# Power.net
KiCad netlist of a schematic drawn in Altium Designer
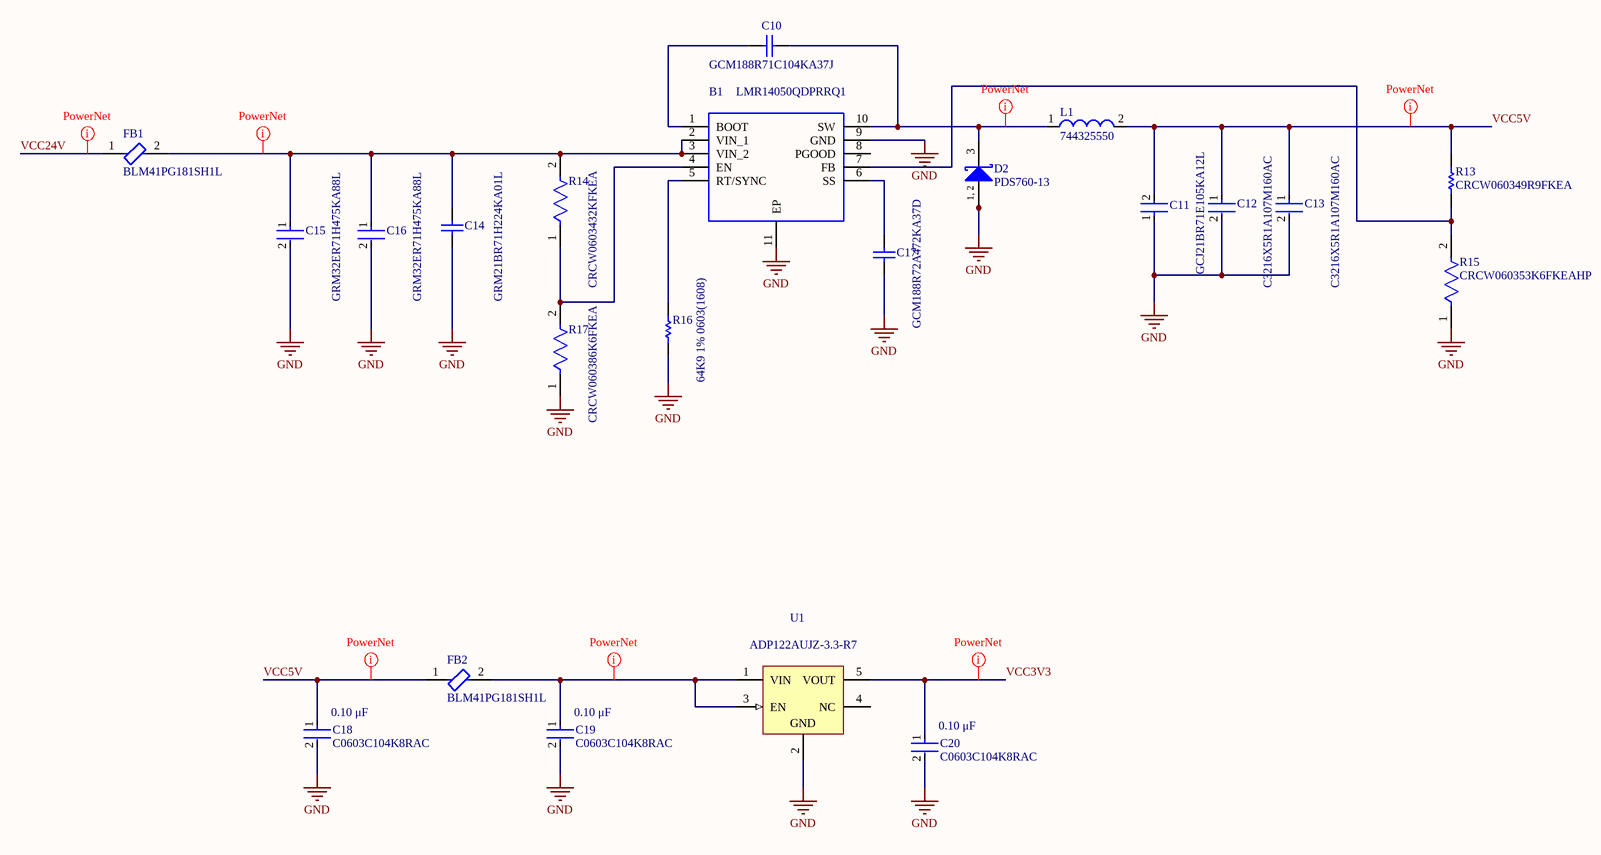
[diagram p0: Power.SchDoc]

(export (version "E")
  (design (tool "Eeschema 10.0.6"))
  (components
    (comp (ref "B1")
      (value "LMR14050QDPRRQ1")
      (footprint "SON80P400X400X80-11N")
      (description "Automotive 40V, 5A SIMPLE SWITCHER&#174;, 2.2MHz Step-Down Regulator with 40uA IQ")
      (fields (field (name "MOUSER PART NUMBER") "595-LMR14050QDPRRQ1"))
      (libsource (lib "Schlib2") (part "LMR14050QDPRRQ1"))
    )
    (comp (ref "C10")
      (value "GCM188R71C104KA37J")
      (footprint "CAPC1608X90X35LL10T15")
      (fields (field (name "MANUFACTURER") "Murata"))
      (libsource (lib "Altium Content Vault") (part "CAP"))
    )
    (comp (ref "C11")
      (value "GCJ21BR71E105KA12L")
      (footprint "FP-GCJ21B-0_3-MFG")
      (description "Multilayer Ceramic Capacitors MLCC - SMD/SMT 0805 1uF 10%, 25VDC,  X7R 15%")
      (fields (field (name "TOLERANCE") "10%"))
      (libsource (lib "Altium Content Vault") (part "02cd4be3c70576c341d710602a673aa"))
    )
    (comp (ref "C12")
      (value "C3216X5R1A107M160AC")
      (footprint "FP-C3216-160-0_3-IPC_C")
      (description "Multilayer Ceramic Capacitors 100uF ±20% 10V X5R SMD 1206")
      (fields (field (name "VOLTAGE") "10V") (field (name "TOLERANCE") "20%"))
      (libsource (lib "Altium Content Vault") (part "02cd4be3c70576c341d710602a673aa"))
    )
    (comp (ref "C13")
      (value "C3216X5R1A107M160AC")
      (footprint "FP-C3216-160-0_3-IPC_C")
      (description "Multilayer Ceramic Capacitors 100uF ±20% 10V X5R SMD 1206")
      (fields (field (name "VOLTAGE") "10V") (field (name "TOLERANCE") "20%"))
      (libsource (lib "Altium Content Vault") (part "02cd4be3c70576c341d710602a673aa"))
    )
    (comp (ref "C14")
      (value "GRM21BR71H224KA01L")
      (footprint "CAPC2013X135X45NL10T25")
      (fields (field (name "MANUFACTURER") "Murata"))
      (libsource (lib "Altium Content Vault") (part "CAP"))
    )
    (comp (ref "C15")
      (value "GRM32ER71H475KA88L")
      (footprint "FP-GRM32-MFG")
      (description "CAP CER 4.7UF 50V X7R 1210")
      (fields (field (name "MANUFACTURER") "Murata") (field (name "TOLERANCE") "10%"))
      (libsource (lib "Altium Content Vault") (part "b4654b650e69147ec39a6b967a45e02"))
    )
    (comp (ref "C16")
      (value "GRM32ER71H475KA88L")
      (footprint "FP-GRM32-MFG")
      (description "CAP CER 4.7UF 50V X7R 1210")
      (fields (field (name "MANUFACTURER") "Murata") (field (name "TOLERANCE") "10%"))
      (libsource (lib "Altium Content Vault") (part "b4654b650e69147ec39a6b967a45e02"))
    )
    (comp (ref "C17")
      (value "GCM188R72A472KA37D")
      (footprint "CAPC1608X90X35ML10T15")
      (fields (field (name "MANUFACTURER") "Murata"))
      (libsource (lib "Altium Content Vault") (part "CAP"))
    )
    (comp (ref "C18")
      (value "C0603C104K8RAC")
      (footprint "FP-C0603C-CF-MFG")
      (description "C0603 0.10 μF X7R 30ppm/°C 10.00% 10 V")
      (fields
        (field (name "MANUFACTURER") "KEMET")
        (field (name "CAPACITANCE") "0.10 μF")
        (field (name "OCTOPART") "https://octopart.com/c0603c104k8rac-kemet-1325403")
      )
      (libsource (lib "Altium Content Vault") (part "b4654b650e69147ec39a6b967a45e02"))
    )
    (comp (ref "C19")
      (value "C0603C104K8RAC")
      (footprint "FP-C0603C-CF-MFG")
      (description "C0603 0.10 μF X7R 30ppm/°C 10.00% 10 V")
      (fields
        (field (name "MANUFACTURER") "KEMET")
        (field (name "CAPACITANCE") "0.10 μF")
        (field (name "OCTOPART") "https://octopart.com/c0603c104k8rac-kemet-1325403")
      )
      (libsource (lib "Altium Content Vault") (part "b4654b650e69147ec39a6b967a45e02"))
    )
    (comp (ref "C20")
      (value "C0603C104K8RAC")
      (footprint "FP-C0603C-CF-MFG")
      (description "C0603 0.10 μF X7R 30ppm/°C 10.00% 10 V")
      (fields
        (field (name "MANUFACTURER") "KEMET")
        (field (name "CAPACITANCE") "0.10 μF")
        (field (name "OCTOPART") "https://octopart.com/c0603c104k8rac-kemet-1325403")
      )
      (libsource (lib "Altium Content Vault") (part "b4654b650e69147ec39a6b967a45e02"))
    )
    (comp (ref "D2")
      (value "PDS760-13")
      (footprint "DIOD-POWERDI5-3_V")
      (description "Schottky Barrier Rectifier, 60 V, 7 A, -65 to 150 degC, 3-Pin SMD, RoHS, Tape and Reel")
      (fields (field (name "MANUFACTURER") "Diodes Inc"))
      (libsource (lib "Altium Content Vault") (part "DSKY-AAK-3_A"))
    )
    (comp (ref "FB1")
      (value "BLM41PG181SH1L")
      (footprint "FP-BLM41-0_2-a1_2-MFG")
      (description "Ferrite Bead, 1806, 180Ω @ 100MHz, 25%, 0.02Ω, 3.5A")
      (fields (field (name "TOLERANCE") "25%"))
      (libsource (lib "Altium Content Vault") (part "5f30dd21d616792df468990f7003faa"))
    )
    (comp (ref "FB2")
      (value "BLM41PG181SH1L")
      (footprint "FP-BLM41-0_2-a1_2-MFG")
      (description "Ferrite Bead, 1806, 180Ω @ 100MHz, 25%, 0.02Ω, 3.5A")
      (fields (field (name "TOLERANCE") "25%"))
      (libsource (lib "Altium Content Vault") (part "5f30dd21d616792df468990f7003faa"))
    )
    (comp (ref "L1")
      (value "744325550")
      (footprint "WE-HCI-1050")
      (description "SMD Flat Wire High Current Inductor WE-HCI, L=5.50 µH")
      (libsource (lib "Altium Content Vault") (part "PAS-IND-INDUCTOR-2"))
    )
    (comp (ref "R13")
      (value "CRCW060349R9FKEA")
      (footprint "RESC1609X50X30ML10T20")
      (fields (field (name "MANUFACTURER") "Vishay Dale"))
      (libsource (lib "Altium Content Vault") (part "RES"))
    )
    (comp (ref "R14")
      (value "CRCW0603432KFKEA")
      (footprint "FP-CRCW0603-e3-MFG")
      (description "RES Thick Film, 432kΩ, 1%, 0.1W, 100ppm/°C, 0603")
      (fields (field (name "TOLERANCE") "1%"))
      (libsource (lib "Altium Content Vault") (part "1029c3af85768c4190bb7ad29bc67b5"))
    )
    (comp (ref "R15")
      (value "CRCW060353K6FKEAHP")
      (footprint "FP-CRCW0603-HPe3-MFG")
      (description "RES Thick Film, 53.6kΩ, 1%, 0.33W, 100ppm/°C, 0603")
      (fields (field (name "TOLERANCE") "1%"))
      (libsource (lib "Altium Content Vault") (part "1029c3af85768c4190bb7ad29bc67b5"))
    )
    (comp (ref "R16")
      (value "64K9 1% 0603(1608)")
      (footprint "RESC0603(1608)_N")
      (description "64K9 0.1W 1% 0603 (1608 Metric)  SMD")
      (fields (field (name "TOLERANCE") "1 %") (field (name "POWER") "0.1 W"))
      (libsource (lib "Altium Content Vault") (part "RES"))
    )
    (comp (ref "R17")
      (value "CRCW060386K6FKEA")
      (footprint "FP-CRCW0603-e3-IPC_B")
      (description "RES Thick Film, 86.6kΩ, 1%, 0.1W, 100ppm/°C, 0603")
      (fields (field (name "TOLERANCE") "1%"))
      (libsource (lib "Altium Content Vault") (part "1029c3af85768c4190bb7ad29bc67b5"))
    )
    (comp (ref "U1")
      (value "ADP122AUJZ-3.3-R7")
      (footprint "ADI-UJ-5_M")
      (fields (field (name "MANUFACTURER") "Analog Devices"))
      (libsource (lib "Altium Content Vault") (part "ADI-ADP1XX-UJ-5"))
    )
  )
  (nets
    (net (code "1") (name "/VCC3V3") (class "Default")
      (node (ref "C20") (pin "1") (pinfunction "1_1") (pintype "passive"))
      (node (ref "U1") (pin "5") (pinfunction "VOUT_5") (pintype "power_in"))
    )
    (net (code "2") (name "/VCC5V") (class "Default")
      (node (ref "C11") (pin "2") (pinfunction "2_2") (pintype "passive"))
      (node (ref "C12") (pin "1") (pinfunction "1_1") (pintype "passive"))
      (node (ref "C13") (pin "1") (pinfunction "1_1") (pintype "passive"))
      (node (ref "C18") (pin "1") (pinfunction "1_1") (pintype "passive"))
      (node (ref "FB2") (pin "1") (pinfunction "1_1") (pintype "passive"))
      (node (ref "L1") (pin "2") (pinfunction "2_2") (pintype "passive"))
      (node (ref "R13") (pin "2") (pinfunction "2_2") (pintype "passive"))
    )
    (net (code "3") (name "/VCC24V") (class "Default")
      (node (ref "FB1") (pin "1") (pinfunction "1_1") (pintype "passive"))
    )
    (net (code "4") (name "GND") (class "Default")
      (node (ref "B1") (pin "11") (pinfunction "EP_11") (pintype "passive"))
      (node (ref "B1") (pin "9") (pinfunction "GND_9") (pintype "passive"))
      (node (ref "C11") (pin "1") (pinfunction "1_1") (pintype "passive"))
      (node (ref "C12") (pin "2") (pinfunction "2_2") (pintype "passive"))
      (node (ref "C13") (pin "2") (pinfunction "2_2") (pintype "passive"))
      (node (ref "C14") (pin "1") (pinfunction "1_1") (pintype "passive"))
      (node (ref "C15") (pin "2") (pinfunction "2_2") (pintype "passive"))
      (node (ref "C16") (pin "2") (pinfunction "2_2") (pintype "passive"))
      (node (ref "C17") (pin "1") (pinfunction "1_1") (pintype "passive"))
      (node (ref "C18") (pin "2") (pinfunction "2_2") (pintype "passive"))
      (node (ref "C19") (pin "2") (pinfunction "2_2") (pintype "passive"))
      (node (ref "C20") (pin "2") (pinfunction "2_2") (pintype "passive"))
      (node (ref "D2") (pin "1") (pinfunction "A_1") (pintype "passive"))
      (node (ref "D2") (pin "2") (pinfunction "A_2") (pintype "passive"))
      (node (ref "R15") (pin "1") (pinfunction "1_1") (pintype "passive"))
      (node (ref "R16") (pin "1") (pinfunction "1_1") (pintype "passive"))
      (node (ref "R17") (pin "1") (pinfunction "1_1") (pintype "passive"))
      (node (ref "U1") (pin "2") (pinfunction "GND_2") (pintype "power_in"))
    )
    (net (code "5") (name "Net-(B1-BOOT)") (class "Default")
      (node (ref "B1") (pin "1") (pinfunction "BOOT_1") (pintype "passive"))
      (node (ref "C10") (pin "1") (pinfunction "1_1") (pintype "passive"))
    )
    (net (code "6") (name "Net-(B1-EN)") (class "Default")
      (node (ref "B1") (pin "4") (pinfunction "EN_4") (pintype "passive"))
      (node (ref "R14") (pin "1") (pinfunction "1_1") (pintype "passive"))
      (node (ref "R17") (pin "2") (pinfunction "2_2") (pintype "passive"))
    )
    (net (code "7") (name "Net-(B1-FB)") (class "Default")
      (node (ref "B1") (pin "7") (pinfunction "FB_7") (pintype "passive"))
      (node (ref "R13") (pin "1") (pinfunction "1_1") (pintype "passive"))
      (node (ref "R15") (pin "2") (pinfunction "2_2") (pintype "passive"))
    )
    (net (code "8") (name "Net-(B1-RT{slash}SYNC)") (class "Default")
      (node (ref "B1") (pin "5") (pinfunction "RT/SYNC_5") (pintype "passive"))
      (node (ref "R16") (pin "2") (pinfunction "2_2") (pintype "passive"))
    )
    (net (code "9") (name "Net-(B1-SS)") (class "Default")
      (node (ref "B1") (pin "6") (pinfunction "SS_6") (pintype "passive"))
      (node (ref "C17") (pin "2") (pinfunction "2_2") (pintype "passive"))
    )
    (net (code "10") (name "Net-(B1-SW)") (class "Default")
      (node (ref "B1") (pin "10") (pinfunction "SW_10") (pintype "passive"))
      (node (ref "C10") (pin "2") (pinfunction "2_2") (pintype "passive"))
      (node (ref "D2") (pin "3") (pinfunction "K_3") (pintype "passive"))
      (node (ref "L1") (pin "1") (pinfunction "1_1") (pintype "passive"))
    )
    (net (code "11") (name "Net-(B1-VIN_1)") (class "Default")
      (node (ref "B1") (pin "2") (pinfunction "VIN_1_2") (pintype "passive"))
      (node (ref "B1") (pin "3") (pinfunction "VIN_2_3") (pintype "passive"))
      (node (ref "C14") (pin "2") (pinfunction "2_2") (pintype "passive"))
      (node (ref "C15") (pin "1") (pinfunction "1_1") (pintype "passive"))
      (node (ref "C16") (pin "1") (pinfunction "1_1") (pintype "passive"))
      (node (ref "FB1") (pin "2") (pinfunction "2_2") (pintype "passive"))
      (node (ref "R14") (pin "2") (pinfunction "2_2") (pintype "passive"))
    )
    (net (code "12") (name "Net-(U1-EN)") (class "Default")
      (node (ref "C19") (pin "1") (pinfunction "1_1") (pintype "passive"))
      (node (ref "FB2") (pin "2") (pinfunction "2_2") (pintype "passive"))
      (node (ref "U1") (pin "1") (pinfunction "VIN_1") (pintype "power_in"))
      (node (ref "U1") (pin "3") (pinfunction "EN_3") (pintype "input"))
    )
    (net (code "13") (name "unconnected-(B1-PGOOD-Pad8)") (class "Default")
      (node (ref "B1") (pin "8") (pinfunction "PGOOD_8") (pintype "passive"))
    )
    (net (code "14") (name "unconnected-(U1-NC-Pad4)") (class "Default")
      (node (ref "U1") (pin "4") (pinfunction "NC_4") (pintype "passive"))
    )
  )
)
